# Port_Controller.net
KiCad netlist of a schematic drawn in Altium Designer
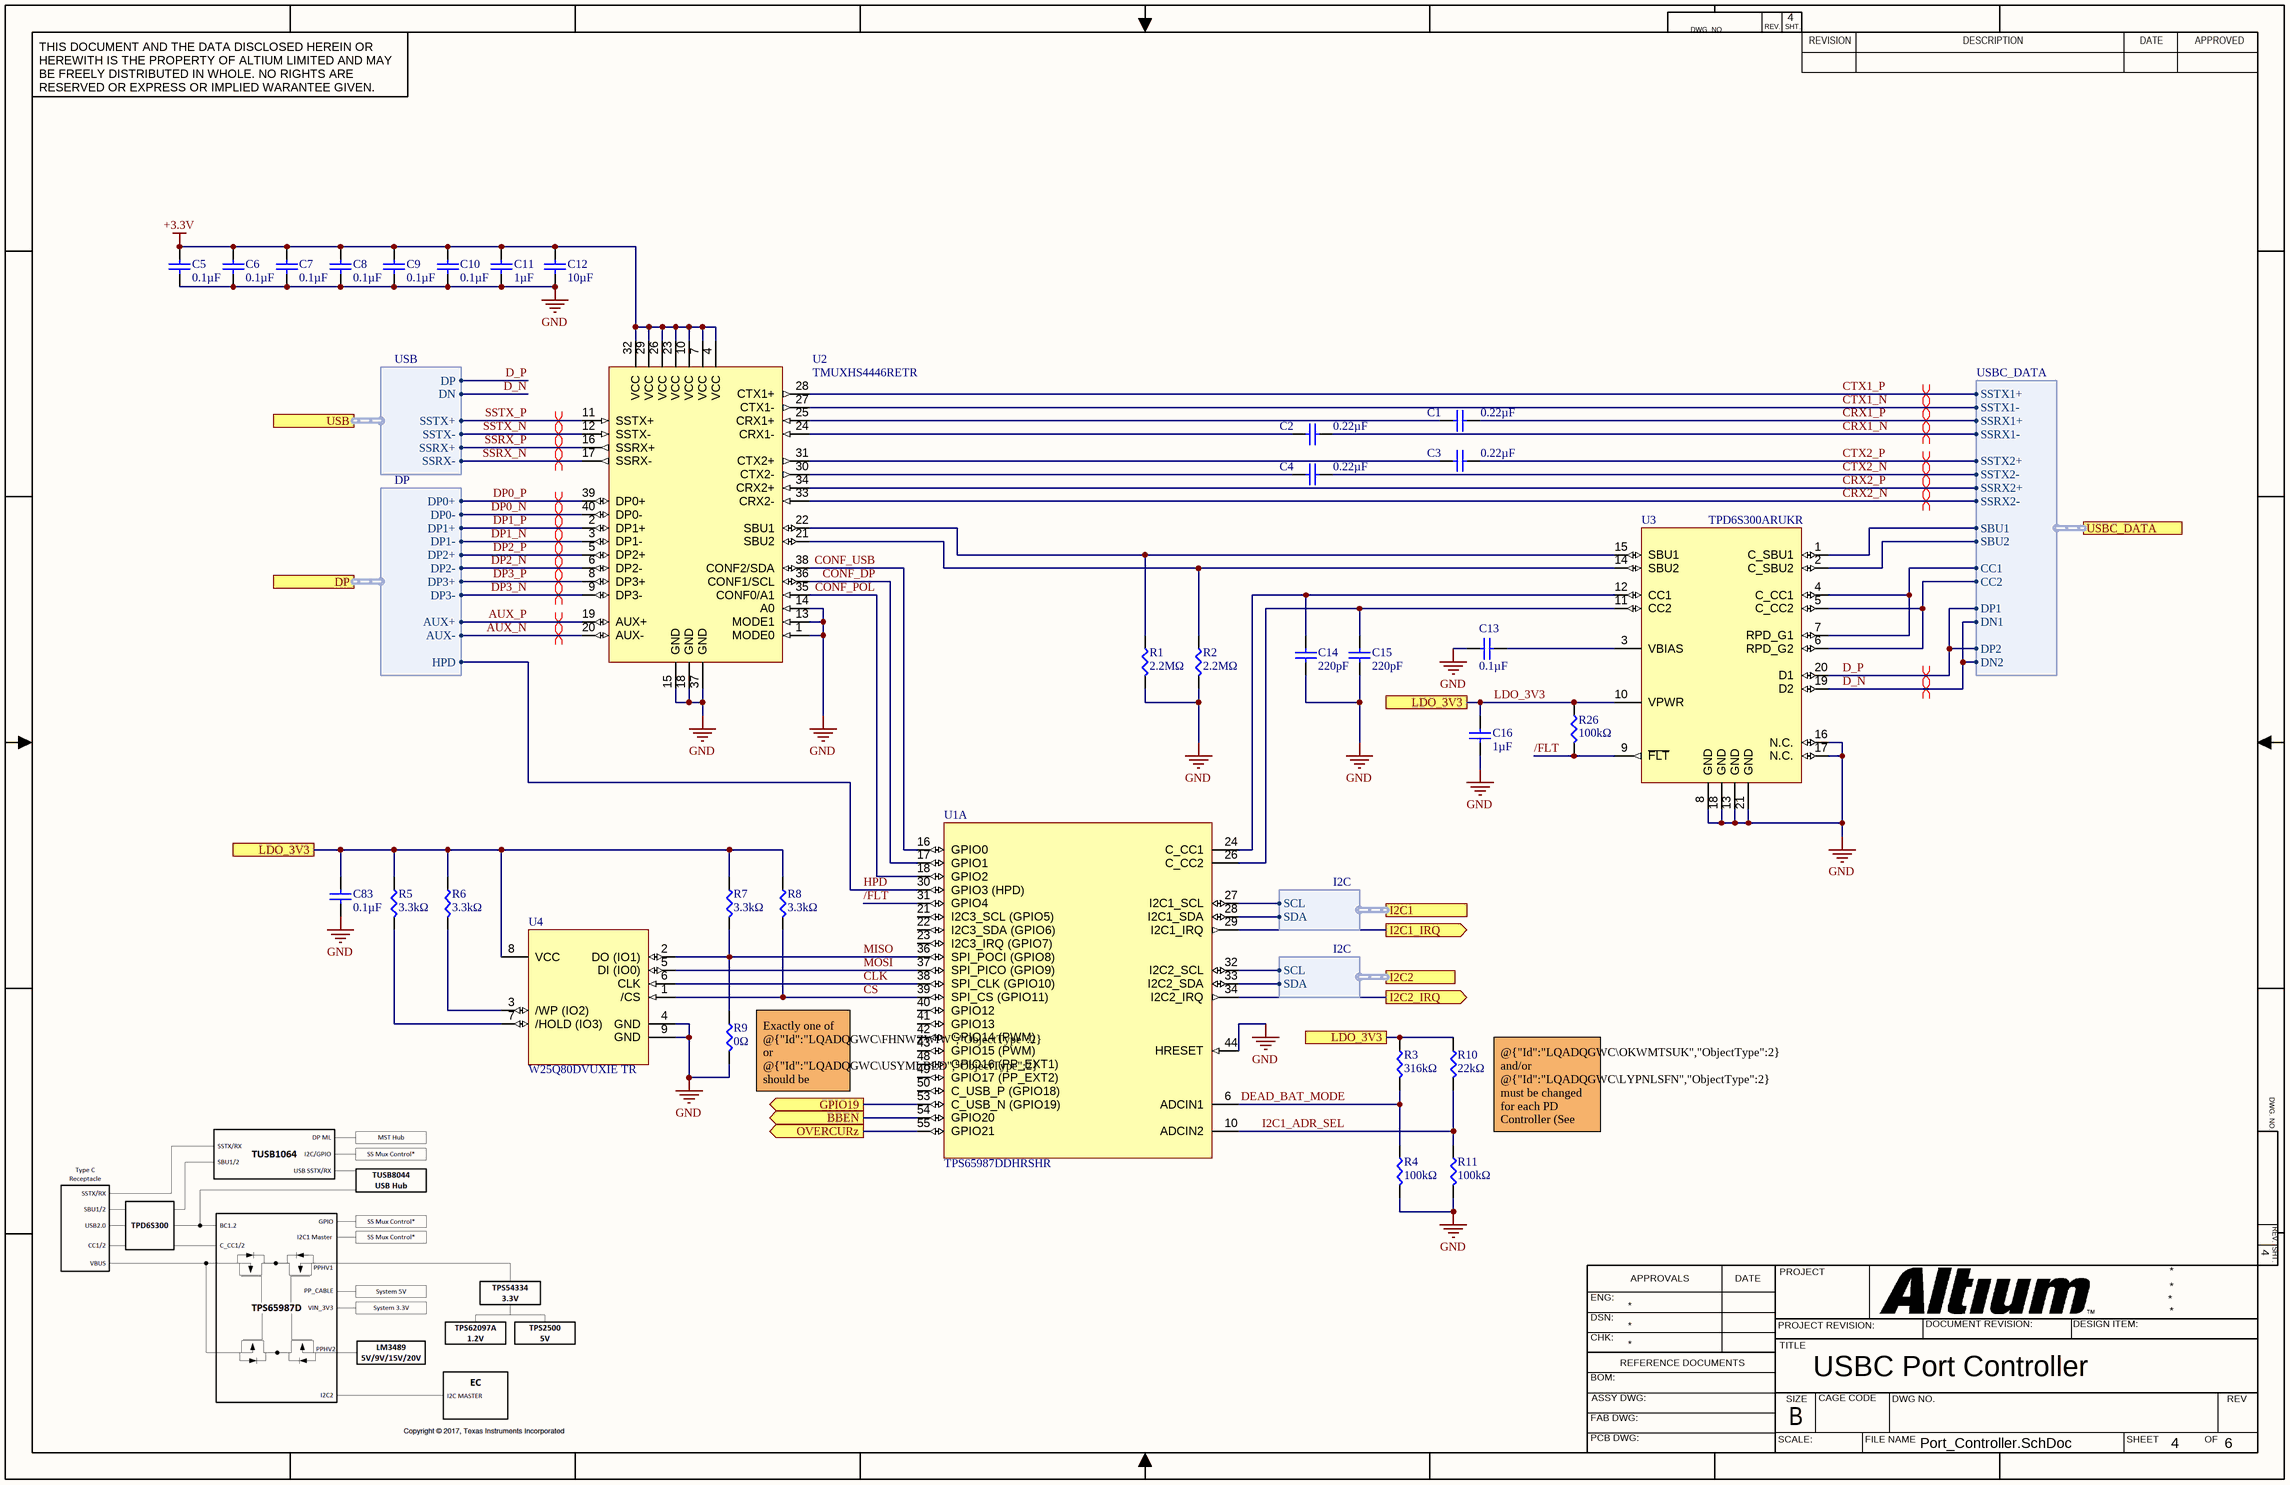
[diagram p0: Port_Controller.SchDoc]

(export (version "E")
  (design (tool "Eeschema 10.0.6"))
  (components
    (comp (ref "C1")
      (value "0.22µF")
      (footprint "CAP0402")
      (description "0.22 µF ±10% 50V Ceramic Capacitor X5R 0402 (1005 Metric)")
      (fields (field (name "VOLTAGE") "50V") (field (name "Comment") "UMK105BJ224KV-F"))
      (libsource (lib "Schlib1") (part "UMK105BJ224KV-F"))
    )
    (comp (ref "C2")
      (value "0.22µF")
      (footprint "CAP0402")
      (description "0.22 µF ±10% 50V Ceramic Capacitor X5R 0402 (1005 Metric)")
      (fields (field (name "VOLTAGE") "50V") (field (name "Comment") "UMK105BJ224KV-F"))
      (libsource (lib "Schlib1") (part "UMK105BJ224KV-F"))
    )
    (comp (ref "C3")
      (value "0.22µF")
      (footprint "CAP0402")
      (description "0.22 µF ±10% 50V Ceramic Capacitor X5R 0402 (1005 Metric)")
      (fields (field (name "VOLTAGE") "50V") (field (name "Comment") "UMK105BJ224KV-F"))
      (libsource (lib "Schlib1") (part "UMK105BJ224KV-F"))
    )
    (comp (ref "C4")
      (value "0.22µF")
      (footprint "CAP0402")
      (description "0.22 µF ±10% 50V Ceramic Capacitor X5R 0402 (1005 Metric)")
      (fields (field (name "VOLTAGE") "50V") (field (name "Comment") "UMK105BJ224KV-F"))
      (libsource (lib "Schlib1") (part "UMK105BJ224KV-F"))
    )
    (comp (ref "C5")
      (value "0.1µF")
      (footprint "CAP0402")
      (description "0.1 µF ±10% 50V Ceramic Capacitor X5R 0402 (1005 Metric)")
      (fields (field (name "VOLTAGE") "50V") (field (name "Comment") "CC0402KRX5R9BB104"))
      (libsource (lib "Schlib1") (part "CC0402KRX5R9BB104"))
    )
    (comp (ref "C6")
      (value "0.1µF")
      (footprint "CAP0402")
      (description "0.1 µF ±10% 50V Ceramic Capacitor X5R 0402 (1005 Metric)")
      (fields (field (name "VOLTAGE") "50V") (field (name "Comment") "CC0402KRX5R9BB104"))
      (libsource (lib "Schlib1") (part "CC0402KRX5R9BB104"))
    )
    (comp (ref "C7")
      (value "0.1µF")
      (footprint "CAP0402")
      (description "0.1 µF ±10% 50V Ceramic Capacitor X5R 0402 (1005 Metric)")
      (fields (field (name "VOLTAGE") "50V") (field (name "Comment") "CC0402KRX5R9BB104"))
      (libsource (lib "Schlib1") (part "CC0402KRX5R9BB104"))
    )
    (comp (ref "C8")
      (value "0.1µF")
      (footprint "CAP0402")
      (description "0.1 µF ±10% 50V Ceramic Capacitor X5R 0402 (1005 Metric)")
      (fields (field (name "VOLTAGE") "50V") (field (name "Comment") "CC0402KRX5R9BB104"))
      (libsource (lib "Schlib1") (part "CC0402KRX5R9BB104"))
    )
    (comp (ref "C9")
      (value "0.1µF")
      (footprint "CAP0402")
      (description "0.1 µF ±10% 50V Ceramic Capacitor X5R 0402 (1005 Metric)")
      (fields (field (name "VOLTAGE") "50V") (field (name "Comment") "CC0402KRX5R9BB104"))
      (libsource (lib "Schlib1") (part "CC0402KRX5R9BB104"))
    )
    (comp (ref "C10")
      (value "0.1µF")
      (footprint "CAP0402")
      (description "0.1 µF ±10% 50V Ceramic Capacitor X5R 0402 (1005 Metric)")
      (fields (field (name "VOLTAGE") "50V") (field (name "Comment") "CC0402KRX5R9BB104"))
      (libsource (lib "Schlib1") (part "CC0402KRX5R9BB104"))
    )
    (comp (ref "C11")
      (value "1µF")
      (footprint "CAP0402")
      (description "1 µF ±10% 50V Ceramic Capacitor X5R 0402 (1005 Metric)")
      (fields (field (name "VOLTAGE") "50V") (field (name "Comment") "GRM155R61H105KE05D"))
      (libsource (lib "Schlib1") (part "GRM155R61H105KE05D"))
    )
    (comp (ref "C12")
      (value "10µF")
      (footprint "CAP0402")
      (description "10 µF ±20% 6.3V Ceramic Capacitor X5R 0402 (1005 Metric)")
      (fields (field (name "VOLTAGE") "6.3V") (field (name "Comment") "CL05A106MQ5NUNC"))
      (libsource (lib "Schlib1") (part "CL05A106MQ5NUNC"))
    )
    (comp (ref "C13")
      (value "0.1µF")
      (footprint "CAP0402")
      (description "0.1 µF ±10% 50V Ceramic Capacitor X5R 0402 (1005 Metric)")
      (fields (field (name "VOLTAGE") "50V") (field (name "Comment") "CC0402KRX5R9BB104"))
      (libsource (lib "Schlib1") (part "CC0402KRX5R9BB104"))
    )
    (comp (ref "C14")
      (value "220pF")
      (footprint "CAP0402")
      (description "220 pF ±5% 50V Ceramic Capacitor C0G, NP0 0402 (1005 Metric)")
      (fields (field (name "VOLTAGE") "50V") (field (name "Comment") "GRM1555C1H221JA01D"))
      (libsource (lib "Schlib1") (part "GRM1555C1H221JA01D"))
    )
    (comp (ref "C15")
      (value "220pF")
      (footprint "CAP0402")
      (description "220 pF ±5% 50V Ceramic Capacitor C0G, NP0 0402 (1005 Metric)")
      (fields (field (name "VOLTAGE") "50V") (field (name "Comment") "GRM1555C1H221JA01D"))
      (libsource (lib "Schlib1") (part "GRM1555C1H221JA01D"))
    )
    (comp (ref "C16")
      (value "1µF")
      (footprint "CAP0402")
      (description "1 µF ±10% 50V Ceramic Capacitor X5R 0402 (1005 Metric)")
      (fields (field (name "VOLTAGE") "50V") (field (name "Comment") "GRM155R61H105KE05D"))
      (libsource (lib "Schlib1") (part "GRM155R61H105KE05D"))
    )
    (comp (ref "C83")
      (value "0.1µF")
      (footprint "CAP0402")
      (description "0.1 µF ±10% 50V Ceramic Capacitor X5R 0402 (1005 Metric)")
      (fields (field (name "VOLTAGE") "50V") (field (name "Comment") "CC0402KRX5R9BB104"))
      (libsource (lib "Schlib1") (part "CC0402KRX5R9BB104"))
    )
    (comp (ref "R1")
      (value "2.2MΩ")
      (footprint "RES0402")
      (description "2.2 MOhms ±1% 0.063W, 1/16W Chip Resistor 0402 (1005 Metric) Moisture Resistant Thick Film")
      (fields (field (name "Comment") "RC0402FR-072M2L"))
      (libsource (lib "Schlib1") (part "RC0402FR-072M2L"))
    )
    (comp (ref "R2")
      (value "2.2MΩ")
      (footprint "RES0402")
      (description "2.2 MOhms ±1% 0.063W, 1/16W Chip Resistor 0402 (1005 Metric) Moisture Resistant Thick Film")
      (fields (field (name "Comment") "RC0402FR-072M2L"))
      (libsource (lib "Schlib1") (part "RC0402FR-072M2L"))
    )
    (comp (ref "R3")
      (value "316kΩ")
      (footprint "RES0402")
      (description "316 kOhms ±1% 0.1W, 1/10W Chip Resistor 0402 (1005 Metric) Automotive AEC-Q200 Thick Film")
      (fields (field (name "Comment") "CRCW0402316KFKED"))
      (libsource (lib "Schlib1") (part "CRCW0402316KFKED"))
    )
    (comp (ref "R4")
      (value "100kΩ")
      (footprint "RES0402")
      (description "100 kOhms ±1% 0.1W, 1/10W Chip Resistor 0402 (1005 Metric) Automotive AEC-Q200 Thick Film")
      (fields (field (name "Comment") "ERJ-2RKF1003X"))
      (libsource (lib "Schlib1") (part "ERJ-2RKF1003X"))
    )
    (comp (ref "R5")
      (value "3.3kΩ")
      (footprint "RES0402")
      (description "3.3 kOhms ±0.1% 0.063W, 1/16W Chip Resistor 0402 (1005 Metric) Automotive AEC-Q200 Thin Film")
      (fields (field (name "Comment") "ERA-2AEB332X"))
      (libsource (lib "Schlib1") (part "ERA-2AEB332X"))
    )
    (comp (ref "R6")
      (value "3.3kΩ")
      (footprint "RES0402")
      (description "3.3 kOhms ±0.1% 0.063W, 1/16W Chip Resistor 0402 (1005 Metric) Automotive AEC-Q200 Thin Film")
      (fields (field (name "Comment") "ERA-2AEB332X"))
      (libsource (lib "Schlib1") (part "ERA-2AEB332X"))
    )
    (comp (ref "R7")
      (value "3.3kΩ")
      (footprint "RES0402")
      (description "3.3 kOhms ±0.1% 0.063W, 1/16W Chip Resistor 0402 (1005 Metric) Automotive AEC-Q200 Thin Film")
      (fields (field (name "Comment") "ERA-2AEB332X"))
      (libsource (lib "Schlib1") (part "ERA-2AEB332X"))
    )
    (comp (ref "R8")
      (value "3.3kΩ")
      (footprint "RES0402")
      (description "3.3 kOhms ±0.1% 0.063W, 1/16W Chip Resistor 0402 (1005 Metric) Automotive AEC-Q200 Thin Film")
      (fields (field (name "Comment") "ERA-2AEB332X"))
      (libsource (lib "Schlib1") (part "ERA-2AEB332X"))
    )
    (comp (ref "R9")
      (value "0Ω")
      (footprint "RES0402")
      (description "0 Ohms Jumper Chip Resistor 0402 (1005 Metric) Moisture Resistant Thick Film")
      (fields (field (name "Comment") "RC0402JR-070RL"))
      (libsource (lib "Schlib1") (part "RC0402JR-070RL"))
    )
    (comp (ref "R10")
      (value "22kΩ")
      (footprint "RES0402")
      (description "22 kOhms ±1% 0.1W, 1/10W Chip Resistor 0402 (1005 Metric) Automotive AEC-Q200 Thick Film")
      (fields (field (name "Comment") "ERJ-2RKF2202X"))
      (libsource (lib "Schlib1") (part "ERJ-2RKF2202X"))
    )
    (comp (ref "R11")
      (value "100kΩ")
      (footprint "RES0402")
      (description "100 kOhms ±1% 0.1W, 1/10W Chip Resistor 0402 (1005 Metric) Automotive AEC-Q200 Thick Film")
      (fields (field (name "Comment") "ERJ-2RKF1003X"))
      (libsource (lib "Schlib1") (part "ERJ-2RKF1003X"))
    )
    (comp (ref "R26")
      (value "100kΩ")
      (footprint "RES0402")
      (description "100 kOhms ±1% 0.1W, 1/10W Chip Resistor 0402 (1005 Metric) Automotive AEC-Q200 Thick Film")
      (fields (field (name "Comment") "ERJ-2RKF1003X"))
      (libsource (lib "Schlib1") (part "ERJ-2RKF1003X"))
    )
    (comp (ref "U1")
      (value "TPS65987DDHRSHR")
      (footprint "56-VQFN (7x7)")
      (description "USB, Type-C Controller PMIC 56-VQFN (7x7)")
      (fields (field (name "MANUFACTURER") "Texas Instruments"))
      (libsource (lib "Schlib1") (part "TPS65987DDHRSHR"))
    )
    (comp (ref "U2")
      (value "TMUXHS4446RETR")
      (footprint "RET0040A")
      (description "4 Circuit IC Switch 4:4 7Ohm (Typ) 40-WQFN (6x3)")
      (fields (field (name "MANUFACTURER") "Texas Instruments"))
      (libsource (lib "Schlib1") (part "TMUXHS4446RETR"))
    )
    (comp (ref "U3")
      (value "TPD6S300ARUKR")
      (footprint "WQFN20_RUK_TEX")
      (description "Overvoltage/Surge Protection IC 8V Internal Switch 20-WQFN (3x3)")
      (fields (field (name "MANUFACTURER") "Texas Instruments"))
      (libsource (lib "Schlib1") (part "TPD6S300ARUKR"))
    )
    (comp (ref "U4")
      (value "W25Q80DVUXIE TR")
      (footprint "USON_3X2_WIN")
      (description "FLASH - NOR Memory IC 8Mbit SPI - Quad I/O 104 MHz 8-USON (2x3)")
      (fields (field (name "MANUFACTURER") "Winbond Electronics"))
      (libsource (lib "Schlib1") (part "W25Q80DVUXIE TR"))
    )
  )
  (nets
    (net (code "5") (name "+3.3V") (class "Default")
      (node (ref "C10") (pin "2") (pinfunction "2_2") (pintype "passive"))
      (node (ref "C11") (pin "2") (pinfunction "2_2") (pintype "passive"))
      (node (ref "C12") (pin "2") (pinfunction "2_2") (pintype "passive"))
      (node (ref "C5") (pin "2") (pinfunction "2_2") (pintype "passive"))
      (node (ref "C6") (pin "2") (pinfunction "2_2") (pintype "passive"))
      (node (ref "C7") (pin "2") (pinfunction "2_2") (pintype "passive"))
      (node (ref "C8") (pin "2") (pinfunction "2_2") (pintype "passive"))
      (node (ref "C9") (pin "2") (pinfunction "2_2") (pintype "passive"))
      (node (ref "U2") (pin "10") (pinfunction "VCC_10") (pintype "passive"))
      (node (ref "U2") (pin "23") (pinfunction "VCC_23") (pintype "passive"))
      (node (ref "U2") (pin "26") (pinfunction "VCC_26") (pintype "passive"))
      (node (ref "U2") (pin "29") (pinfunction "VCC_29") (pintype "passive"))
      (node (ref "U2") (pin "32") (pinfunction "VCC_32") (pintype "passive"))
      (node (ref "U2") (pin "4") (pinfunction "VCC_4") (pintype "passive"))
      (node (ref "U2") (pin "7") (pinfunction "VCC_7") (pintype "passive"))
    )
    (net (code "6") (name "/AUX_N") (class "Default")
      (node (ref "U2") (pin "20") (pinfunction "AUX-_20") (pintype "bidirectional"))
    )
    (net (code "7") (name "/AUX_P") (class "Default")
      (node (ref "U2") (pin "19") (pinfunction "AUX+_19") (pintype "bidirectional"))
    )
    (net (code "8") (name "/BBEN") (class "Default")
      (node (ref "U1") (pin "54") (pinfunction "GPIO20_54") (pintype "bidirectional"))
    )
    (net (code "9") (name "/CC1") (class "Default")
      (node (ref "U3") (pin "4") (pinfunction "C_CC1_4") (pintype "bidirectional"))
      (node (ref "U3") (pin "7") (pinfunction "RPD_G1_7") (pintype "bidirectional"))
    )
    (net (code "10") (name "/CC2") (class "Default")
      (node (ref "U3") (pin "5") (pinfunction "C_CC2_5") (pintype "bidirectional"))
      (node (ref "U3") (pin "6") (pinfunction "RPD_G2_6") (pintype "bidirectional"))
    )
    (net (code "11") (name "/CLK") (class "Default")
      (node (ref "U1") (pin "38") (pinfunction "SPI_CLK_(GPIO10)_38") (pintype "bidirectional"))
      (node (ref "U4") (pin "6") (pinfunction "CLK_6") (pintype "input"))
    )
    (net (code "12") (name "/CONF_DP") (class "Default")
      (node (ref "U1") (pin "17") (pinfunction "GPIO1_17") (pintype "bidirectional"))
      (node (ref "U2") (pin "36") (pinfunction "CONF1/SCL_36") (pintype "bidirectional"))
    )
    (net (code "13") (name "/CONF_POL") (class "Default")
      (node (ref "U1") (pin "18") (pinfunction "GPIO2_18") (pintype "bidirectional"))
      (node (ref "U2") (pin "35") (pinfunction "CONF0/A1_35") (pintype "input"))
    )
    (net (code "14") (name "/CONF_USB") (class "Default")
      (node (ref "U1") (pin "16") (pinfunction "GPIO0_16") (pintype "bidirectional"))
      (node (ref "U2") (pin "38") (pinfunction "CONF2/SDA_38") (pintype "bidirectional"))
    )
    (net (code "15") (name "/CRX1_N") (class "Default")
      (node (ref "C2") (pin "2") (pinfunction "2_2") (pintype "passive"))
    )
    (net (code "16") (name "/CRX1_P") (class "Default")
      (node (ref "C1") (pin "2") (pinfunction "2_2") (pintype "passive"))
    )
    (net (code "17") (name "/CRX2_N") (class "Default")
      (node (ref "U2") (pin "33") (pinfunction "CRX2-_33") (pintype "input"))
    )
    (net (code "18") (name "/CRX2_P") (class "Default")
      (node (ref "U2") (pin "34") (pinfunction "CRX2+_34") (pintype "input"))
    )
    (net (code "19") (name "/CS") (class "Default")
      (node (ref "R8") (pin "1") (pinfunction "1_1") (pintype "passive"))
      (node (ref "U1") (pin "39") (pinfunction "SPI_CS_(GPIO11)_39") (pintype "bidirectional"))
      (node (ref "U4") (pin "1") (pinfunction "/CS_1") (pintype "input"))
    )
    (net (code "20") (name "/CTX1_N") (class "Default")
      (node (ref "U2") (pin "27") (pinfunction "CTX1-_27") (pintype "output"))
    )
    (net (code "21") (name "/CTX1_P") (class "Default")
      (node (ref "U2") (pin "28") (pinfunction "CTX1+_28") (pintype "output"))
    )
    (net (code "22") (name "/CTX2_N") (class "Default")
      (node (ref "C4") (pin "2") (pinfunction "2_2") (pintype "passive"))
    )
    (net (code "23") (name "/CTX2_P") (class "Default")
      (node (ref "C3") (pin "2") (pinfunction "2_2") (pintype "passive"))
    )
    (net (code "24") (name "/DEAD_BAT_MODE") (class "Default")
      (node (ref "R3") (pin "1") (pinfunction "1_1") (pintype "passive"))
      (node (ref "R4") (pin "2") (pinfunction "2_2") (pintype "passive"))
      (node (ref "U1") (pin "6") (pinfunction "ADCIN1_6") (pintype "passive"))
    )
    (net (code "25") (name "/DP0_N") (class "Default")
      (node (ref "U2") (pin "40") (pinfunction "DP0-_40") (pintype "bidirectional"))
    )
    (net (code "26") (name "/DP0_P") (class "Default")
      (node (ref "U2") (pin "39") (pinfunction "DP0+_39") (pintype "bidirectional"))
    )
    (net (code "27") (name "/DP1_N") (class "Default")
      (node (ref "U2") (pin "3") (pinfunction "DP1-_3") (pintype "bidirectional"))
    )
    (net (code "28") (name "/DP1_P") (class "Default")
      (node (ref "U2") (pin "2") (pinfunction "DP1+_2") (pintype "bidirectional"))
    )
    (net (code "29") (name "/DP2_N") (class "Default")
      (node (ref "U2") (pin "6") (pinfunction "DP2-_6") (pintype "bidirectional"))
    )
    (net (code "30") (name "/DP2_P") (class "Default")
      (node (ref "U2") (pin "5") (pinfunction "DP2+_5") (pintype "bidirectional"))
    )
    (net (code "31") (name "/DP3_N") (class "Default")
      (node (ref "U2") (pin "9") (pinfunction "DP3-_9") (pintype "bidirectional"))
    )
    (net (code "32") (name "/DP3_P") (class "Default")
      (node (ref "U2") (pin "8") (pinfunction "DP3+_8") (pintype "bidirectional"))
    )
    (net (code "33") (name "/D_N") (class "Default")
      (node (ref "U3") (pin "19") (pinfunction "D2_19") (pintype "bidirectional"))
    )
    (net (code "34") (name "/D_P") (class "Default")
      (node (ref "U3") (pin "20") (pinfunction "D1_20") (pintype "bidirectional"))
    )
    (net (code "35") (name "/GPIO19") (class "Default")
      (node (ref "U1") (pin "53") (pinfunction "C_USB_N_(GPIO19)_53") (pintype "bidirectional"))
    )
    (net (code "36") (name "/HPD") (class "Default")
      (node (ref "U1") (pin "30") (pinfunction "GPIO3_(HPD)_30") (pintype "bidirectional"))
    )
    (net (code "37") (name "/I2C1_ADR_SEL") (class "Default")
      (node (ref "R10") (pin "1") (pinfunction "1_1") (pintype "passive"))
      (node (ref "R11") (pin "2") (pinfunction "2_2") (pintype "passive"))
      (node (ref "U1") (pin "10") (pinfunction "ADCIN2_10") (pintype "passive"))
    )
    (net (code "38") (name "/I2C1_IRQ") (class "Default")
      (node (ref "U1") (pin "29") (pinfunction "I2C1_IRQ_29") (pintype "output"))
    )
    (net (code "39") (name "/I2C2_IRQ") (class "Default")
      (node (ref "U1") (pin "34") (pinfunction "I2C2_IRQ_34") (pintype "output"))
    )
    (net (code "40") (name "/LDO_3V3") (class "Default")
      (node (ref "C16") (pin "2") (pinfunction "2_2") (pintype "passive"))
      (node (ref "C83") (pin "2") (pinfunction "2_2") (pintype "passive"))
      (node (ref "R10") (pin "2") (pinfunction "2_2") (pintype "passive"))
      (node (ref "R26") (pin "2") (pinfunction "2_2") (pintype "passive"))
      (node (ref "R3") (pin "2") (pinfunction "2_2") (pintype "passive"))
      (node (ref "R5") (pin "2") (pinfunction "2_2") (pintype "passive"))
      (node (ref "R6") (pin "2") (pinfunction "2_2") (pintype "passive"))
      (node (ref "R7") (pin "2") (pinfunction "2_2") (pintype "passive"))
      (node (ref "R8") (pin "2") (pinfunction "2_2") (pintype "passive"))
      (node (ref "U3") (pin "10") (pinfunction "VPWR_10") (pintype "passive"))
      (node (ref "U4") (pin "8") (pinfunction "VCC_8") (pintype "passive"))
    )
    (net (code "41") (name "/MISO") (class "Default")
      (node (ref "R7") (pin "1") (pinfunction "1_1") (pintype "passive"))
      (node (ref "R9") (pin "2") (pinfunction "2_2") (pintype "passive"))
      (node (ref "U1") (pin "36") (pinfunction "SPI_POCI_(GPIO8)_36") (pintype "bidirectional"))
      (node (ref "U4") (pin "2") (pinfunction "DO_(IO1)_2") (pintype "bidirectional"))
    )
    (net (code "42") (name "/MOSI") (class "Default")
      (node (ref "U1") (pin "37") (pinfunction "SPI_PICO_(GPIO9)_37") (pintype "bidirectional"))
      (node (ref "U4") (pin "5") (pinfunction "DI_(IO0)_5") (pintype "bidirectional"))
    )
    (net (code "43") (name "/OVERCURz") (class "Default")
      (node (ref "U1") (pin "55") (pinfunction "GPIO21_55") (pintype "bidirectional"))
    )
    (net (code "44") (name "/SBU1") (class "Default")
      (node (ref "U3") (pin "1") (pinfunction "C_SBU1_1") (pintype "bidirectional"))
    )
    (net (code "45") (name "/SBU2") (class "Default")
      (node (ref "U3") (pin "2") (pinfunction "C_SBU2_2") (pintype "bidirectional"))
    )
    (net (code "46") (name "/SSRX_N") (class "Default")
      (node (ref "U2") (pin "17") (pinfunction "SSRX-_17") (pintype "output"))
    )
    (net (code "47") (name "/SSRX_P") (class "Default")
      (node (ref "U2") (pin "16") (pinfunction "SSRX+_16") (pintype "output"))
    )
    (net (code "48") (name "/SSTX_N") (class "Default")
      (node (ref "U2") (pin "12") (pinfunction "SSTX-_12") (pintype "input"))
    )
    (net (code "49") (name "/SSTX_P") (class "Default")
      (node (ref "U2") (pin "11") (pinfunction "SSTX+_11") (pintype "input"))
    )
    (net (code "54") (name "/{slash}FLT") (class "Default")
      (node (ref "R26") (pin "1") (pinfunction "1_1") (pintype "passive"))
      (node (ref "U1") (pin "31") (pinfunction "GPIO4_31") (pintype "bidirectional"))
      (node (ref "U3") (pin "9") (pinfunction "~{FLT}_9") (pintype "output"))
    )
    (net (code "55") (name "GND") (class "Default")
      (node (ref "C10") (pin "1") (pinfunction "1_1") (pintype "passive"))
      (node (ref "C11") (pin "1") (pinfunction "1_1") (pintype "passive"))
      (node (ref "C12") (pin "1") (pinfunction "1_1") (pintype "passive"))
      (node (ref "C13") (pin "1") (pinfunction "1_1") (pintype "passive"))
      (node (ref "C14") (pin "1") (pinfunction "1_1") (pintype "passive"))
      (node (ref "C15") (pin "1") (pinfunction "1_1") (pintype "passive"))
      (node (ref "C16") (pin "1") (pinfunction "1_1") (pintype "passive"))
      (node (ref "C5") (pin "1") (pinfunction "1_1") (pintype "passive"))
      (node (ref "C6") (pin "1") (pinfunction "1_1") (pintype "passive"))
      (node (ref "C7") (pin "1") (pinfunction "1_1") (pintype "passive"))
      (node (ref "C8") (pin "1") (pinfunction "1_1") (pintype "passive"))
      (node (ref "C83") (pin "1") (pinfunction "1_1") (pintype "passive"))
      (node (ref "C9") (pin "1") (pinfunction "1_1") (pintype "passive"))
      (node (ref "R1") (pin "1") (pinfunction "1_1") (pintype "passive"))
      (node (ref "R11") (pin "1") (pinfunction "1_1") (pintype "passive"))
      (node (ref "R2") (pin "1") (pinfunction "1_1") (pintype "passive"))
      (node (ref "R4") (pin "1") (pinfunction "1_1") (pintype "passive"))
      (node (ref "R9") (pin "1") (pinfunction "1_1") (pintype "passive"))
      (node (ref "U1") (pin "44") (pinfunction "HRESET_44") (pintype "input"))
      (node (ref "U2") (pin "1") (pinfunction "MODE0_1") (pintype "input"))
      (node (ref "U2") (pin "13") (pinfunction "MODE1_13") (pintype "input"))
      (node (ref "U2") (pin "14") (pinfunction "A0_14") (pintype "input"))
      (node (ref "U2") (pin "15") (pinfunction "GND_15") (pintype "passive"))
      (node (ref "U2") (pin "18") (pinfunction "GND_18") (pintype "passive"))
      (node (ref "U2") (pin "37") (pinfunction "GND_37") (pintype "passive"))
      (node (ref "U3") (pin "13") (pinfunction "GND_13") (pintype "passive"))
      (node (ref "U3") (pin "16") (pinfunction "N.C._16") (pintype "bidirectional"))
      (node (ref "U3") (pin "17") (pinfunction "N.C._17") (pintype "bidirectional"))
      (node (ref "U3") (pin "18") (pinfunction "GND_18") (pintype "passive"))
      (node (ref "U3") (pin "21") (pinfunction "GND_21") (pintype "passive"))
      (node (ref "U3") (pin "8") (pinfunction "GND_8") (pintype "passive"))
      (node (ref "U4") (pin "4") (pinfunction "GND_4") (pintype "passive"))
      (node (ref "U4") (pin "9") (pinfunction "GND_9") (pintype "passive"))
    )
    (net (code "56") (name "Net-(U1A-C_CC1)") (class "Default")
      (node (ref "C14") (pin "2") (pinfunction "2_2") (pintype "passive"))
      (node (ref "U1") (pin "24") (pinfunction "C_CC1_24") (pintype "passive"))
      (node (ref "U3") (pin "12") (pinfunction "CC1_12") (pintype "bidirectional"))
    )
    (net (code "57") (name "Net-(U1A-C_CC2)") (class "Default")
      (node (ref "C15") (pin "2") (pinfunction "2_2") (pintype "passive"))
      (node (ref "U1") (pin "26") (pinfunction "C_CC2_26") (pintype "passive"))
      (node (ref "U3") (pin "11") (pinfunction "CC2_11") (pintype "bidirectional"))
    )
    (net (code "58") (name "Net-(U2-CRX1+)") (class "Default")
      (node (ref "C1") (pin "1") (pinfunction "1_1") (pintype "passive"))
      (node (ref "U2") (pin "25") (pinfunction "CRX1+_25") (pintype "input"))
    )
    (net (code "59") (name "Net-(U2-CRX1-)") (class "Default")
      (node (ref "C2") (pin "1") (pinfunction "1_1") (pintype "passive"))
      (node (ref "U2") (pin "24") (pinfunction "CRX1-_24") (pintype "input"))
    )
    (net (code "60") (name "Net-(U2-CTX2+)") (class "Default")
      (node (ref "C3") (pin "1") (pinfunction "1_1") (pintype "passive"))
      (node (ref "U2") (pin "31") (pinfunction "CTX2+_31") (pintype "output"))
    )
    (net (code "61") (name "Net-(U2-CTX2-)") (class "Default")
      (node (ref "C4") (pin "1") (pinfunction "1_1") (pintype "passive"))
      (node (ref "U2") (pin "30") (pinfunction "CTX2-_30") (pintype "output"))
    )
    (net (code "62") (name "Net-(U2-SBU1)") (class "Default")
      (node (ref "R1") (pin "2") (pinfunction "2_2") (pintype "passive"))
      (node (ref "U2") (pin "22") (pinfunction "SBU1_22") (pintype "bidirectional"))
      (node (ref "U3") (pin "15") (pinfunction "SBU1_15") (pintype "bidirectional"))
    )
    (net (code "63") (name "Net-(U2-SBU2)") (class "Default")
      (node (ref "R2") (pin "2") (pinfunction "2_2") (pintype "passive"))
      (node (ref "U2") (pin "21") (pinfunction "SBU2_21") (pintype "bidirectional"))
      (node (ref "U3") (pin "14") (pinfunction "SBU2_14") (pintype "bidirectional"))
    )
    (net (code "64") (name "Net-(U3-VBIAS)") (class "Default")
      (node (ref "C13") (pin "2") (pinfunction "2_2") (pintype "passive"))
      (node (ref "U3") (pin "3") (pinfunction "VBIAS_3") (pintype "passive"))
    )
    (net (code "65") (name "Net-(U4-{slash}HOLD_(IO3))") (class "Default")
      (node (ref "R5") (pin "1") (pinfunction "1_1") (pintype "passive"))
      (node (ref "U4") (pin "7") (pinfunction "/HOLD_(IO3)_7") (pintype "bidirectional"))
    )
    (net (code "66") (name "Net-(U4-{slash}WP_(IO2))") (class "Default")
      (node (ref "R6") (pin "1") (pinfunction "1_1") (pintype "passive"))
      (node (ref "U4") (pin "3") (pinfunction "/WP_(IO2)_3") (pintype "bidirectional"))
    )
    (net (code "67") (name "unconnected-(U1A-C_USB_P_(GPIO18)-Pad50)") (class "Default")
      (node (ref "U1") (pin "50") (pinfunction "C_USB_P_(GPIO18)_50") (pintype "bidirectional"))
    )
    (net (code "68") (name "unconnected-(U1A-GPIO12-Pad40)") (class "Default")
      (node (ref "U1") (pin "40") (pinfunction "GPIO12_40") (pintype "bidirectional"))
    )
    (net (code "69") (name "unconnected-(U1A-GPIO13-Pad41)") (class "Default")
      (node (ref "U1") (pin "41") (pinfunction "GPIO13_41") (pintype "bidirectional"))
    )
    (net (code "70") (name "unconnected-(U1A-GPIO14_(PWM)-Pad42)") (class "Default")
      (node (ref "U1") (pin "42") (pinfunction "GPIO14_(PWM)_42") (pintype "bidirectional"))
    )
    (net (code "71") (name "unconnected-(U1A-GPIO15_(PWM)-Pad43)") (class "Default")
      (node (ref "U1") (pin "43") (pinfunction "GPIO15_(PWM)_43") (pintype "bidirectional"))
    )
    (net (code "72") (name "unconnected-(U1A-GPIO16_(PP_EXT1)-Pad48)") (class "Default")
      (node (ref "U1") (pin "48") (pinfunction "GPIO16_(PP_EXT1)_48") (pintype "bidirectional"))
    )
    (net (code "73") (name "unconnected-(U1A-GPIO17_(PP_EXT2)-Pad49)") (class "Default")
      (node (ref "U1") (pin "49") (pinfunction "GPIO17_(PP_EXT2)_49") (pintype "bidirectional"))
    )
    (net (code "74") (name "unconnected-(U1A-I2C1_SCL-Pad27)") (class "Default")
      (node (ref "U1") (pin "27") (pinfunction "I2C1_SCL_27") (pintype "bidirectional"))
    )
    (net (code "75") (name "unconnected-(U1A-I2C1_SDA-Pad28)") (class "Default")
      (node (ref "U1") (pin "28") (pinfunction "I2C1_SDA_28") (pintype "bidirectional"))
    )
    (net (code "76") (name "unconnected-(U1A-I2C2_SCL-Pad32)") (class "Default")
      (node (ref "U1") (pin "32") (pinfunction "I2C2_SCL_32") (pintype "bidirectional"))
    )
    (net (code "77") (name "unconnected-(U1A-I2C2_SDA-Pad33)") (class "Default")
      (node (ref "U1") (pin "33") (pinfunction "I2C2_SDA_33") (pintype "bidirectional"))
    )
    (net (code "78") (name "unconnected-(U1A-I2C3_IRQ_(GPIO7)-Pad23)") (class "Default")
      (node (ref "U1") (pin "23") (pinfunction "I2C3_IRQ_(GPIO7)_23") (pintype "bidirectional"))
    )
    (net (code "79") (name "unconnected-(U1A-I2C3_SCL_(GPIO5)-Pad21)") (class "Default")
      (node (ref "U1") (pin "21") (pinfunction "I2C3_SCL_(GPIO5)_21") (pintype "bidirectional"))
    )
    (net (code "80") (name "unconnected-(U1A-I2C3_SDA_(GPIO6)-Pad22)") (class "Default")
      (node (ref "U1") (pin "22") (pinfunction "I2C3_SDA_(GPIO6)_22") (pintype "bidirectional"))
    )
  )
)
